# fader_ver2.net
KiCad netlist of a schematic drawn in EAGLE
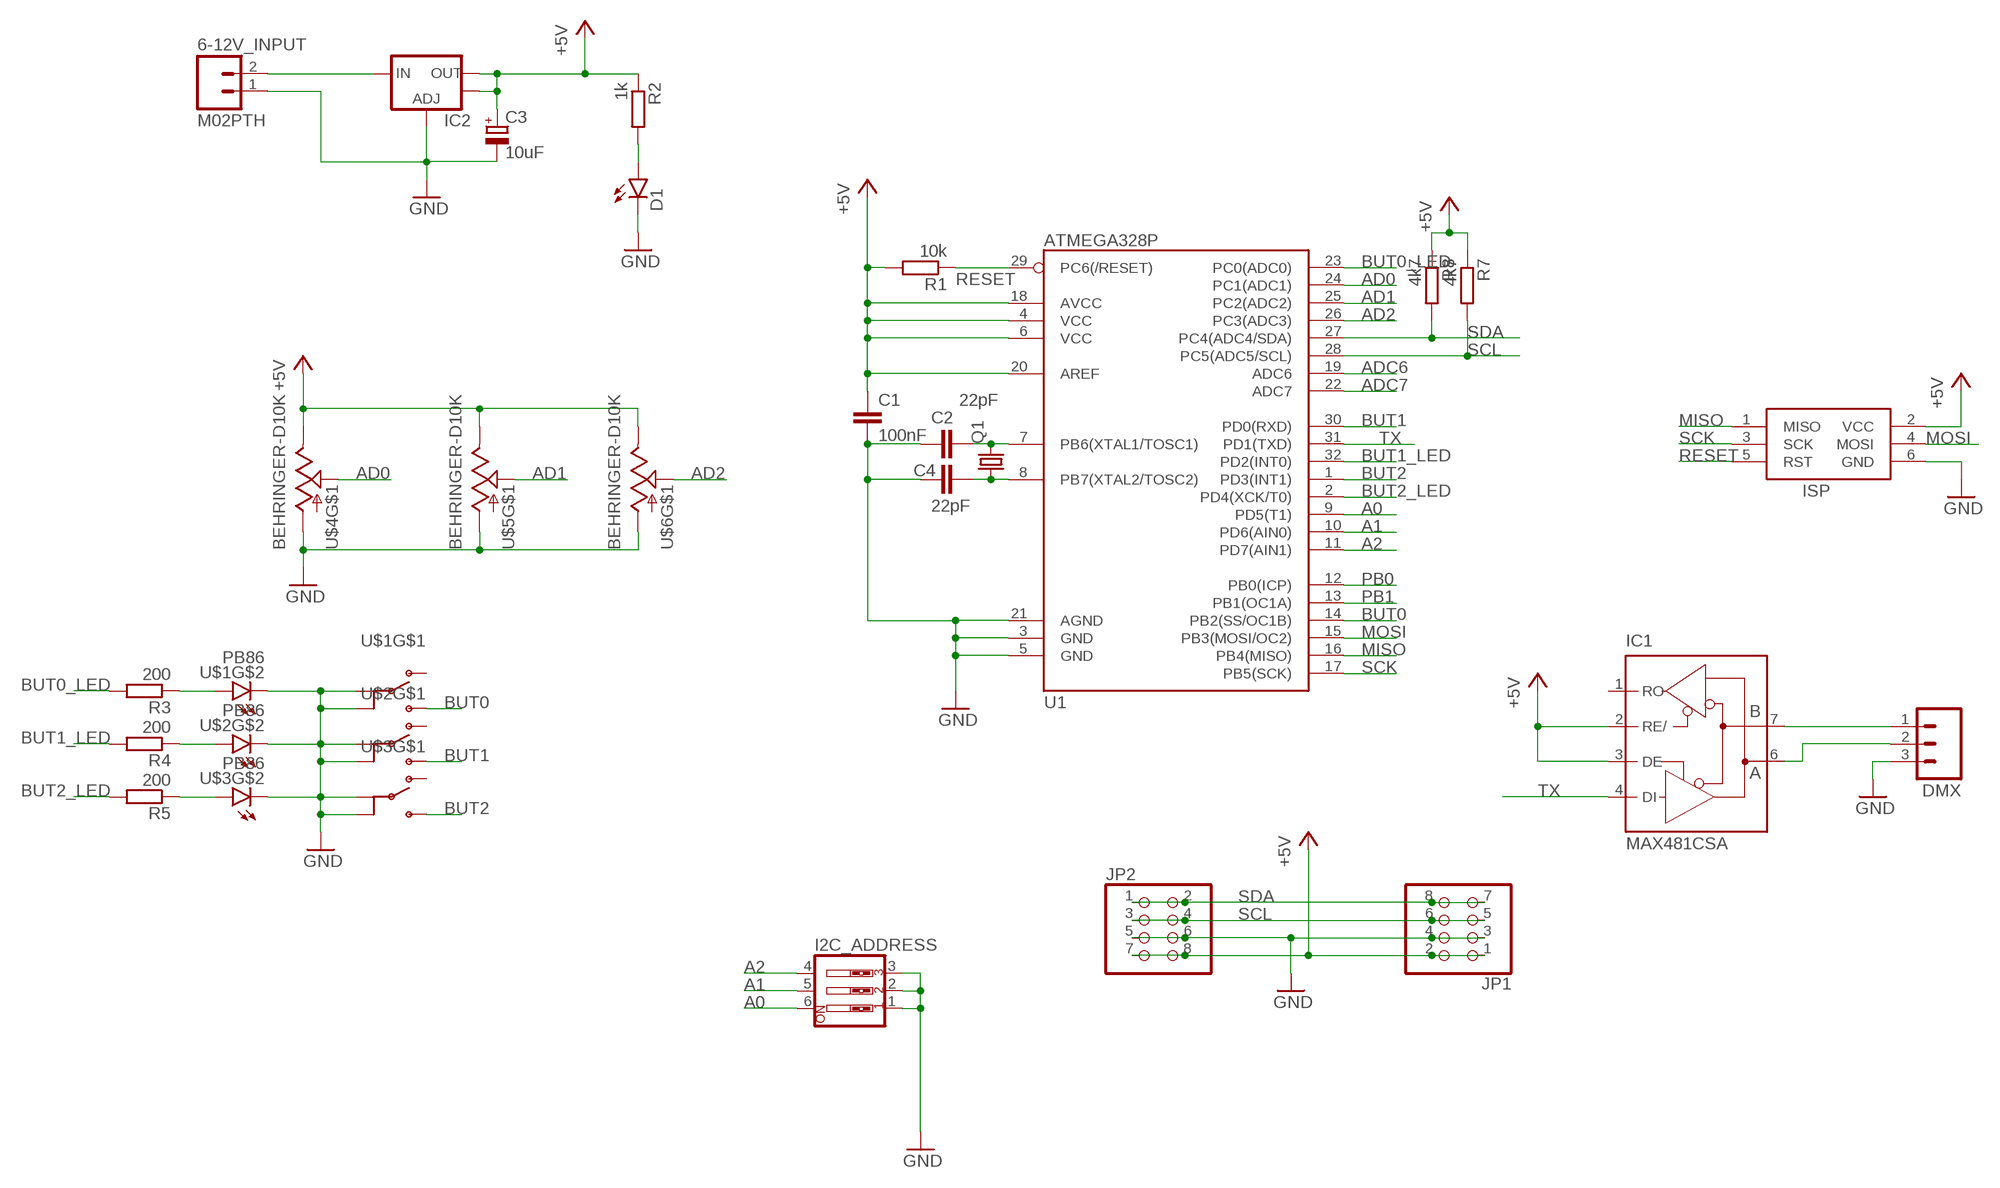
[diagram p0: schematic, sheet 1]

(export (version "E")
  (design (tool "Eeschema 10.0.6"))
  (components
    (comp (ref "6-12V_INPUT")
      (value "M02PTH")
      (footprint "eagle-import:1X02")
      (libsource (lib "eagle-import") (part "M02PTH"))
    )
    (comp (ref "C1")
      (value "100nF")
      (footprint "eagle-import:C0603")
      (libsource (lib "eagle-import") (part "C-EUC0603"))
    )
    (comp (ref "C2")
      (value "22pF")
      (footprint "eagle-import:C0603")
      (libsource (lib "eagle-import") (part "C-EUC0603"))
    )
    (comp (ref "C3")
      (value "10uF")
      (footprint "eagle-import:CT6032")
      (libsource (lib "eagle-import") (part "CPOL-EUCT6032"))
    )
    (comp (ref "C4")
      (value "22pF")
      (footprint "eagle-import:C0603")
      (libsource (lib "eagle-import") (part "C-EUC0603"))
    )
    (comp (ref "D1")
      (value "LED")
      (footprint "eagle-import:LED-3528MM")
      (libsource (lib "eagle-import") (part "LED"))
    )
    (comp (ref "DMX")
      (value "M03PTH")
      (footprint "eagle-import:1X03")
      (libsource (lib "eagle-import") (part "M03PTH"))
    )
    (comp (ref "I2C_ADDRESS")
      (value "SW_DIP-3")
      (footprint "eagle-import:EDG-03")
      (libsource (lib "eagle-import") (part "SW_DIP-3"))
    )
    (comp (ref "IC1")
      (value "MAX481CSA")
      (footprint "eagle-import:SO08")
      (fields (field (name "MF") "MAXIM"))
      (libsource (lib "eagle-import") (part "MAX481CSA"))
    )
    (comp (ref "IC2")
      (value "V_REG_LM1117SOT223")
      (footprint "eagle-import:SOT223")
      (libsource (lib "eagle-import") (part "V_REG_LM1117SOT223"))
    )
    (comp (ref "ISP")
      (value "AVRISP-6")
      (footprint "eagle-import:AVRISP")
      (libsource (lib "eagle-import") (part "AVRISP-6"))
    )
    (comp (ref "JP1")
      (value "PINHD-2X4/90")
      (footprint "eagle-import:2X04_90")
      (libsource (lib "eagle-import") (part "PINHD-2X4/90"))
    )
    (comp (ref "JP2")
      (value "PINHD-2X4/90")
      (footprint "eagle-import:2X04_90")
      (libsource (lib "eagle-import") (part "PINHD-2X4/90"))
    )
    (comp (ref "Q1")
      (value "CRYSTALHC49UP")
      (footprint "eagle-import:HC49UP")
      (libsource (lib "eagle-import") (part "CRYSTALHC49UP"))
    )
    (comp (ref "R1")
      (value "10k")
      (footprint "eagle-import:R0603")
      (libsource (lib "eagle-import") (part "R-EU_R0603"))
    )
    (comp (ref "R2")
      (value "1k")
      (footprint "eagle-import:R0603")
      (libsource (lib "eagle-import") (part "R-EU_R0603"))
    )
    (comp (ref "R3")
      (value "200")
      (footprint "eagle-import:R0603")
      (libsource (lib "eagle-import") (part "R-EU_R0603"))
    )
    (comp (ref "R4")
      (value "200")
      (footprint "eagle-import:R0603")
      (libsource (lib "eagle-import") (part "R-EU_R0603"))
    )
    (comp (ref "R5")
      (value "200")
      (footprint "eagle-import:R0603")
      (libsource (lib "eagle-import") (part "R-EU_R0603"))
    )
    (comp (ref "R7")
      (value "4k7")
      (footprint "eagle-import:R0603")
      (libsource (lib "eagle-import") (part "R-EU_R0603"))
    )
    (comp (ref "R8")
      (value "4k7")
      (footprint "eagle-import:R0603")
      (libsource (lib "eagle-import") (part "R-EU_R0603"))
    )
    (comp (ref "U$1")
      (value "PB86")
      (footprint "eagle-import:PB86")
      (libsource (lib "eagle-import") (part "PB86"))
    )
    (comp (ref "U$2")
      (value "PB86")
      (footprint "eagle-import:PB86")
      (libsource (lib "eagle-import") (part "PB86"))
    )
    (comp (ref "U$3")
      (value "PB86")
      (footprint "eagle-import:PB86")
      (libsource (lib "eagle-import") (part "PB86"))
    )
    (comp (ref "U$4")
      (value "BEHRINGER-D10K")
      (footprint "eagle-import:BEHRINGER_D10K")
      (libsource (lib "eagle-import") (part "BEHRINGER-D10K"))
    )
    (comp (ref "U$5")
      (value "BEHRINGER-D10K")
      (footprint "eagle-import:BEHRINGER_D10K")
      (libsource (lib "eagle-import") (part "BEHRINGER-D10K"))
    )
    (comp (ref "U$6")
      (value "BEHRINGER-D10K")
      (footprint "eagle-import:BEHRINGER_D10K")
      (libsource (lib "eagle-import") (part "BEHRINGER-D10K"))
    )
    (comp (ref "U1")
      (value "ATMEGA328P")
      (footprint "eagle-import:TQFP32-08")
      (libsource (lib "eagle-import") (part "ATMEGA328_SMT"))
    )
  )
  (nets
    (net (code "1") (name "+5V") (class "Default")
      (node (ref "C1") (pin "1") (pinfunction "1_1") (pintype "passive"))
      (node (ref "C3") (pin "+") (pinfunction "+_+") (pintype "passive"))
      (node (ref "IC1") (pin "2") (pinfunction "RE/_2") (pintype "input"))
      (node (ref "IC1") (pin "3") (pinfunction "DE_3") (pintype "input"))
      (node (ref "IC2") (pin "2") (pinfunction "OUT_2") (pintype "output"))
      (node (ref "IC2") (pin "4") (pinfunction "OUT_4") (pintype "output"))
      (node (ref "ISP") (pin "2") (pinfunction "VCC_2") (pintype "power_in"))
      (node (ref "JP1") (pin "1") (pinfunction "1_1") (pintype "passive"))
      (node (ref "JP1") (pin "2") (pinfunction "2_2") (pintype "passive"))
      (node (ref "JP2") (pin "7") (pinfunction "7_7") (pintype "passive"))
      (node (ref "JP2") (pin "8") (pinfunction "8_8") (pintype "passive"))
      (node (ref "R1") (pin "2") (pinfunction "2_2") (pintype "passive"))
      (node (ref "R2") (pin "1") (pinfunction "1_1") (pintype "passive"))
      (node (ref "R7") (pin "1") (pinfunction "1_1") (pintype "passive"))
      (node (ref "R8") (pin "1") (pinfunction "1_1") (pintype "passive"))
      (node (ref "U$4") (pin "P$5") (pinfunction "1_P$5") (pintype "passive"))
      (node (ref "U$5") (pin "P$5") (pinfunction "1_P$5") (pintype "passive"))
      (node (ref "U$6") (pin "P$5") (pinfunction "1_P$5") (pintype "passive"))
      (node (ref "U1") (pin "18") (pinfunction "AVCC_18") (pintype "bidirectional"))
      (node (ref "U1") (pin "20") (pinfunction "AREF_20") (pintype "bidirectional"))
      (node (ref "U1") (pin "4") (pinfunction "VCC_4") (pintype "bidirectional"))
      (node (ref "U1") (pin "6") (pinfunction "VCC_6") (pintype "bidirectional"))
    )
    (net (code "2") (name "/A0") (class "Default")
      (node (ref "I2C_ADDRESS") (pin "6") (pinfunction "6_6") (pintype "passive"))
      (node (ref "U1") (pin "9") (pinfunction "PD5(T1)_9") (pintype "bidirectional"))
    )
    (net (code "3") (name "/A1") (class "Default")
      (node (ref "I2C_ADDRESS") (pin "5") (pinfunction "5_5") (pintype "passive"))
      (node (ref "U1") (pin "10") (pinfunction "PD6(AIN0)_10") (pintype "bidirectional"))
    )
    (net (code "4") (name "/A2") (class "Default")
      (node (ref "I2C_ADDRESS") (pin "4") (pinfunction "4_4") (pintype "passive"))
      (node (ref "U1") (pin "11") (pinfunction "PD7(AIN1)_11") (pintype "bidirectional"))
    )
    (net (code "5") (name "/AD0") (class "Default")
      (node (ref "U$4") (pin "P$2") (pinfunction "2_P$2") (pintype "passive"))
      (node (ref "U1") (pin "24") (pinfunction "PC1(ADC1)_24") (pintype "bidirectional"))
    )
    (net (code "6") (name "/AD1") (class "Default")
      (node (ref "U$5") (pin "P$2") (pinfunction "2_P$2") (pintype "passive"))
      (node (ref "U1") (pin "25") (pinfunction "PC2(ADC2)_25") (pintype "bidirectional"))
    )
    (net (code "7") (name "/AD2") (class "Default")
      (node (ref "U$6") (pin "P$2") (pinfunction "2_P$2") (pintype "passive"))
      (node (ref "U1") (pin "26") (pinfunction "PC3(ADC3)_26") (pintype "bidirectional"))
    )
    (net (code "8") (name "/ADC6") (class "Default")
      (node (ref "U1") (pin "19") (pinfunction "ADC6_19") (pintype "bidirectional"))
    )
    (net (code "9") (name "/ADC7") (class "Default")
      (node (ref "U1") (pin "22") (pinfunction "ADC7_22") (pintype "bidirectional"))
    )
    (net (code "10") (name "/BUT0") (class "Default")
      (node (ref "U$1") (pin "2") (pinfunction "NO_2") (pintype "passive"))
      (node (ref "U1") (pin "14") (pinfunction "PB2(SS/OC1B)_14") (pintype "bidirectional"))
    )
    (net (code "11") (name "/BUT0_LED") (class "Default")
      (node (ref "R3") (pin "2") (pinfunction "2_2") (pintype "passive"))
      (node (ref "U1") (pin "23") (pinfunction "PC0(ADC0)_23") (pintype "bidirectional"))
    )
    (net (code "12") (name "/BUT1") (class "Default")
      (node (ref "U$2") (pin "2") (pinfunction "NO_2") (pintype "passive"))
      (node (ref "U1") (pin "30") (pinfunction "PD0(RXD)_30") (pintype "bidirectional"))
    )
    (net (code "13") (name "/BUT1_LED") (class "Default")
      (node (ref "R4") (pin "2") (pinfunction "2_2") (pintype "passive"))
      (node (ref "U1") (pin "32") (pinfunction "PD2(INT0)_32") (pintype "bidirectional"))
    )
    (net (code "14") (name "/BUT2") (class "Default")
      (node (ref "U$3") (pin "2") (pinfunction "NO_2") (pintype "passive"))
      (node (ref "U1") (pin "1") (pinfunction "PD3(INT1)_1") (pintype "bidirectional"))
    )
    (net (code "15") (name "/BUT2_LED") (class "Default")
      (node (ref "R5") (pin "2") (pinfunction "2_2") (pintype "passive"))
      (node (ref "U1") (pin "2") (pinfunction "PD4(XCK/T0)_2") (pintype "bidirectional"))
    )
    (net (code "16") (name "/MISO") (class "Default")
      (node (ref "ISP") (pin "1") (pinfunction "MISO_1") (pintype "input"))
      (node (ref "U1") (pin "16") (pinfunction "PB4(MISO)_16") (pintype "bidirectional"))
    )
    (net (code "17") (name "/MOSI") (class "Default")
      (node (ref "ISP") (pin "4") (pinfunction "MOSI_4") (pintype "output"))
      (node (ref "U1") (pin "15") (pinfunction "PB3(MOSI/OC2)_15") (pintype "bidirectional"))
    )
    (net (code "18") (name "/PB0") (class "Default")
      (node (ref "U1") (pin "12") (pinfunction "PB0(ICP)_12") (pintype "bidirectional"))
    )
    (net (code "19") (name "/PB1") (class "Default")
      (node (ref "U1") (pin "13") (pinfunction "PB1(OC1A)_13") (pintype "bidirectional"))
    )
    (net (code "20") (name "/RESET") (class "Default")
      (node (ref "ISP") (pin "5") (pinfunction "RST_5") (pintype "output"))
      (node (ref "R1") (pin "1") (pinfunction "1_1") (pintype "passive"))
      (node (ref "U1") (pin "29") (pinfunction "PC6(/RESET)_29") (pintype "bidirectional"))
    )
    (net (code "21") (name "/SCK") (class "Default")
      (node (ref "ISP") (pin "3") (pinfunction "SCK_3") (pintype "output"))
      (node (ref "U1") (pin "17") (pinfunction "PB5(SCK)_17") (pintype "bidirectional"))
    )
    (net (code "22") (name "/SCL") (class "Default")
      (node (ref "JP1") (pin "5") (pinfunction "5_5") (pintype "passive"))
      (node (ref "JP1") (pin "6") (pinfunction "6_6") (pintype "passive"))
      (node (ref "JP2") (pin "3") (pinfunction "3_3") (pintype "passive"))
      (node (ref "JP2") (pin "4") (pinfunction "4_4") (pintype "passive"))
      (node (ref "R7") (pin "2") (pinfunction "2_2") (pintype "passive"))
      (node (ref "U1") (pin "28") (pinfunction "PC5(ADC5/SCL)_28") (pintype "bidirectional"))
    )
    (net (code "23") (name "/SDA") (class "Default")
      (node (ref "JP1") (pin "7") (pinfunction "7_7") (pintype "passive"))
      (node (ref "JP1") (pin "8") (pinfunction "8_8") (pintype "passive"))
      (node (ref "JP2") (pin "1") (pinfunction "1_1") (pintype "passive"))
      (node (ref "JP2") (pin "2") (pinfunction "2_2") (pintype "passive"))
      (node (ref "R8") (pin "2") (pinfunction "2_2") (pintype "passive"))
      (node (ref "U1") (pin "27") (pinfunction "PC4(ADC4/SDA)_27") (pintype "bidirectional"))
    )
    (net (code "24") (name "/TX") (class "Default")
      (node (ref "IC1") (pin "4") (pinfunction "DI_4") (pintype "input"))
      (node (ref "U1") (pin "31") (pinfunction "PD1(TXD)_31") (pintype "bidirectional"))
    )
    (net (code "25") (name "GND") (class "Default")
      (node (ref "6-12V_INPUT") (pin "1") (pinfunction "1_1") (pintype "passive"))
      (node (ref "C1") (pin "2") (pinfunction "2_2") (pintype "passive"))
      (node (ref "C2") (pin "1") (pinfunction "1_1") (pintype "passive"))
      (node (ref "C3") (pin "-") (pinfunction "-_-") (pintype "passive"))
      (node (ref "C4") (pin "1") (pinfunction "1_1") (pintype "passive"))
      (node (ref "D1") (pin "C") (pinfunction "C_C") (pintype "passive"))
      (node (ref "DMX") (pin "3") (pinfunction "3_3") (pintype "passive"))
      (node (ref "I2C_ADDRESS") (pin "1") (pinfunction "1_1") (pintype "passive"))
      (node (ref "I2C_ADDRESS") (pin "2") (pinfunction "2_2") (pintype "passive"))
      (node (ref "I2C_ADDRESS") (pin "3") (pinfunction "3_3") (pintype "passive"))
      (node (ref "IC2") (pin "1") (pinfunction "ADJ_1") (pintype "input"))
      (node (ref "ISP") (pin "6") (pinfunction "GND_6") (pintype "power_in"))
      (node (ref "JP1") (pin "3") (pinfunction "3_3") (pintype "passive"))
      (node (ref "JP1") (pin "4") (pinfunction "4_4") (pintype "passive"))
      (node (ref "JP2") (pin "5") (pinfunction "5_5") (pintype "passive"))
      (node (ref "JP2") (pin "6") (pinfunction "6_6") (pintype "passive"))
      (node (ref "U$1") (pin "1_1") (pinfunction "IN1_1_1") (pintype "passive"))
      (node (ref "U$1") (pin "1_2") (pinfunction "IN2_1_2") (pintype "passive"))
      (node (ref "U$1") (pin "L3") (pinfunction "C_L3") (pintype "passive"))
      (node (ref "U$2") (pin "1_1") (pinfunction "IN1_1_1") (pintype "passive"))
      (node (ref "U$2") (pin "1_2") (pinfunction "IN2_1_2") (pintype "passive"))
      (node (ref "U$2") (pin "L3") (pinfunction "C_L3") (pintype "passive"))
      (node (ref "U$3") (pin "1_1") (pinfunction "IN1_1_1") (pintype "passive"))
      (node (ref "U$3") (pin "1_2") (pinfunction "IN2_1_2") (pintype "passive"))
      (node (ref "U$3") (pin "L3") (pinfunction "C_L3") (pintype "passive"))
      (node (ref "U$4") (pin "P$3") (pinfunction "3_P$3") (pintype "passive"))
      (node (ref "U$5") (pin "P$3") (pinfunction "3_P$3") (pintype "passive"))
      (node (ref "U$6") (pin "P$3") (pinfunction "3_P$3") (pintype "passive"))
      (node (ref "U1") (pin "21") (pinfunction "AGND_21") (pintype "bidirectional"))
      (node (ref "U1") (pin "3") (pinfunction "GND_3") (pintype "bidirectional"))
      (node (ref "U1") (pin "5") (pinfunction "GND_5") (pintype "bidirectional"))
    )
    (net (code "26") (name "Net-(D1-PadA)") (class "Default")
      (node (ref "D1") (pin "A") (pinfunction "A_A") (pintype "passive"))
      (node (ref "R2") (pin "2") (pinfunction "2_2") (pintype "passive"))
    )
    (net (code "27") (name "Net-(IC1A-A)") (class "Default")
      (node (ref "DMX") (pin "2") (pinfunction "2_2") (pintype "passive"))
      (node (ref "IC1") (pin "6") (pinfunction "A_6") (pintype "passive"))
    )
    (net (code "28") (name "Net-(IC1A-B)") (class "Default")
      (node (ref "DMX") (pin "1") (pinfunction "1_1") (pintype "passive"))
      (node (ref "IC1") (pin "7") (pinfunction "B_7") (pintype "passive"))
    )
    (net (code "29") (name "Net-(IC2-IN)") (class "Default")
      (node (ref "6-12V_INPUT") (pin "2") (pinfunction "2_2") (pintype "passive"))
      (node (ref "IC2") (pin "3") (pinfunction "IN_3") (pintype "input"))
    )
    (net (code "30") (name "Net-(U$1B-A)") (class "Default")
      (node (ref "R3") (pin "1") (pinfunction "1_1") (pintype "passive"))
      (node (ref "U$1") (pin "L2") (pinfunction "A_L2") (pintype "passive"))
    )
    (net (code "31") (name "Net-(U$2B-A)") (class "Default")
      (node (ref "R4") (pin "1") (pinfunction "1_1") (pintype "passive"))
      (node (ref "U$2") (pin "L2") (pinfunction "A_L2") (pintype "passive"))
    )
    (net (code "32") (name "Net-(U$3B-A)") (class "Default")
      (node (ref "R5") (pin "1") (pinfunction "1_1") (pintype "passive"))
      (node (ref "U$3") (pin "L2") (pinfunction "A_L2") (pintype "passive"))
    )
    (net (code "33") (name "Net-(U1-PB6(XTAL1{slash}TOSC1))") (class "Default")
      (node (ref "C2") (pin "2") (pinfunction "2_2") (pintype "passive"))
      (node (ref "Q1") (pin "2") (pinfunction "2_2") (pintype "passive"))
      (node (ref "U1") (pin "7") (pinfunction "PB6(XTAL1/TOSC1)_7") (pintype "bidirectional"))
    )
    (net (code "34") (name "Net-(U1-PB7(XTAL2{slash}TOSC2))") (class "Default")
      (node (ref "C4") (pin "2") (pinfunction "2_2") (pintype "passive"))
      (node (ref "Q1") (pin "1") (pinfunction "1_1") (pintype "passive"))
      (node (ref "U1") (pin "8") (pinfunction "PB7(XTAL2/TOSC2)_8") (pintype "bidirectional"))
    )
    (net (code "35") (name "unconnected-(IC1A-RO-Pad1)") (class "Default")
      (node (ref "IC1") (pin "1") (pinfunction "RO_1") (pintype "output"))
    )
    (net (code "36") (name "unconnected-(U$1A-NC-Pad3)") (class "Default")
      (node (ref "U$1") (pin "3") (pinfunction "NC_3") (pintype "passive"))
    )
    (net (code "37") (name "unconnected-(U$2A-NC-Pad3)") (class "Default")
      (node (ref "U$2") (pin "3") (pinfunction "NC_3") (pintype "passive"))
    )
    (net (code "38") (name "unconnected-(U$3A-NC-Pad3)") (class "Default")
      (node (ref "U$3") (pin "3") (pinfunction "NC_3") (pintype "passive"))
    )
  )
)
